# BareBonesArduino.net
KiCad netlist of a schematic drawn in EAGLE
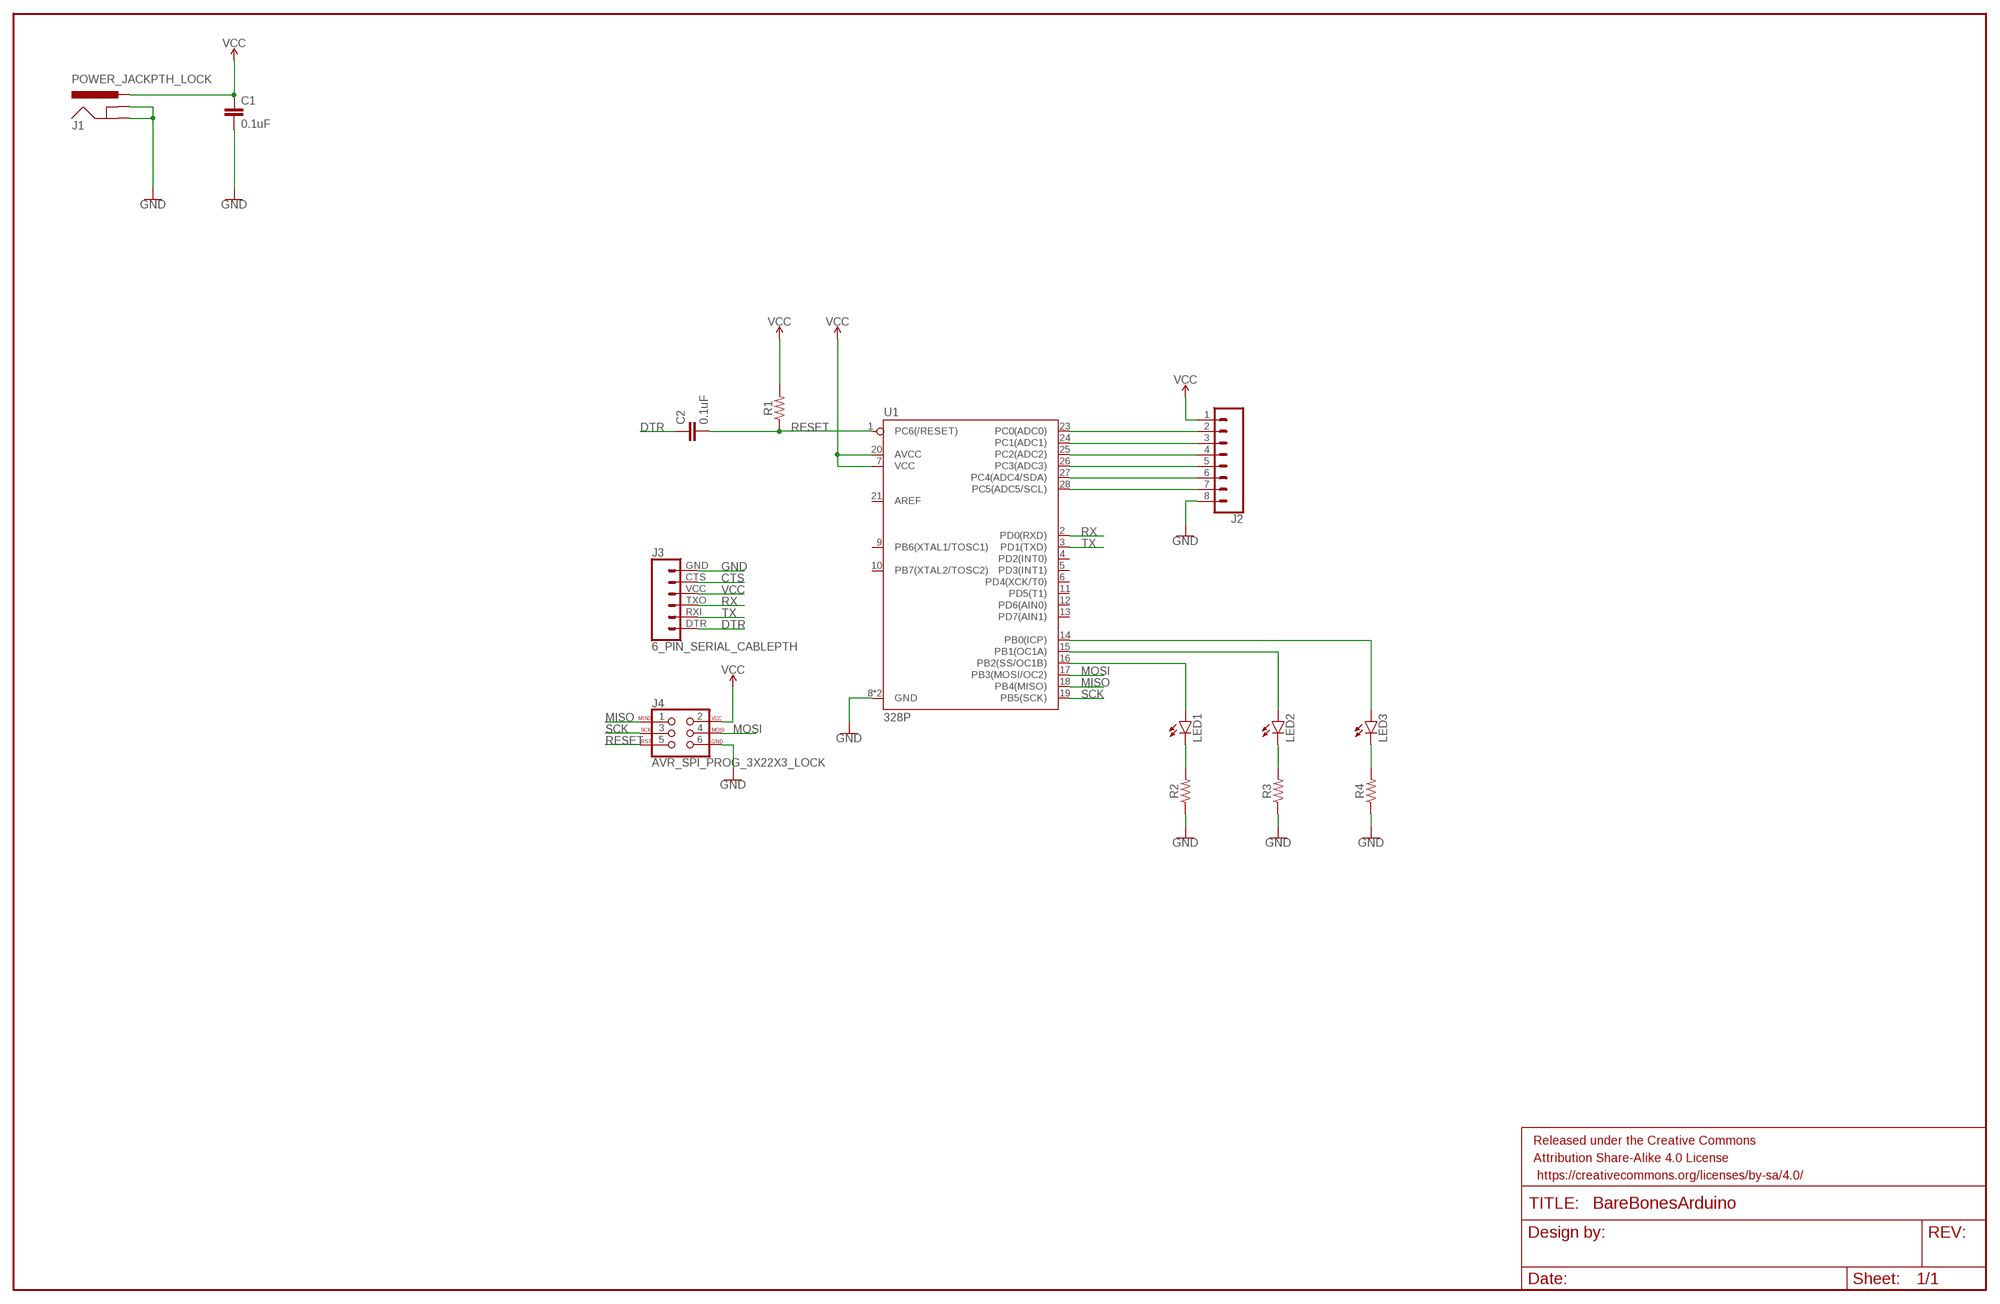
[diagram p0: schematic, sheet 1]

(export (version "E")
  (design (tool "Eeschema 10.0.6"))
  (components
    (comp (ref "C1")
      (value "0.1uF")
      (footprint "eagle-import:CAP-PTH-SMALL-KIT")
      (libsource (lib "eagle-import") (part "0.1UF-KIT-EZ-50V-20%"))
    )
    (comp (ref "C2")
      (value "0.1uF")
      (footprint "eagle-import:CAP-PTH-SMALL-KIT")
      (libsource (lib "eagle-import") (part "0.1UF-KIT-EZ-50V-20%"))
    )
    (comp (ref "FRAME1")
      (value "FRAME-LEDGER")
      (footprint "eagle-import:CREATIVE_COMMONS")
      (libsource (lib "eagle-import") (part "FRAME-LEDGER"))
    )
    (comp (ref "J1")
      (value "POWER_JACKPTH_LOCK")
      (footprint "eagle-import:POWER_JACK_PTH_LOCK")
      (libsource (lib "eagle-import") (part "POWER_JACKPTH_LOCK"))
    )
    (comp (ref "J2")
      (value "CONN_08\"")
      (footprint "eagle-import:1X08")
      (libsource (lib "eagle-import") (part "CONN_08{dblquote}"))
    )
    (comp (ref "J3")
      (value "6_PIN_SERIAL_CABLEPTH")
      (footprint "eagle-import:FTDI_BASIC")
      (libsource (lib "eagle-import") (part "6_PIN_SERIAL_CABLEPTH"))
    )
    (comp (ref "J4")
      (value "AVR_SPI_PROG_3X22X3_LOCK")
      (footprint "eagle-import:2X3_LOCK")
      (libsource (lib "eagle-import") (part "AVR_SPI_PROG_3X22X3_LOCK"))
    )
    (comp (ref "LED1")
      (value "LED5MM")
      (footprint "eagle-import:LED5MM")
      (libsource (lib "eagle-import") (part "LED5MM"))
    )
    (comp (ref "LED2")
      (value "LED5MM")
      (footprint "eagle-import:LED5MM")
      (libsource (lib "eagle-import") (part "LED5MM"))
    )
    (comp (ref "LED3")
      (value "LED5MM")
      (footprint "eagle-import:LED5MM")
      (libsource (lib "eagle-import") (part "LED5MM"))
    )
    (comp (ref "R1")
      (value "RESISTORAXIAL-0.3")
      (footprint "eagle-import:AXIAL-0.3")
      (libsource (lib "eagle-import") (part "RESISTORAXIAL-0.3"))
    )
    (comp (ref "R2")
      (value "RESISTORAXIAL-0.3")
      (footprint "eagle-import:AXIAL-0.3")
      (libsource (lib "eagle-import") (part "RESISTORAXIAL-0.3"))
    )
    (comp (ref "R3")
      (value "RESISTORAXIAL-0.3")
      (footprint "eagle-import:AXIAL-0.3")
      (libsource (lib "eagle-import") (part "RESISTORAXIAL-0.3"))
    )
    (comp (ref "R4")
      (value "RESISTORAXIAL-0.3")
      (footprint "eagle-import:AXIAL-0.3")
      (libsource (lib "eagle-import") (part "RESISTORAXIAL-0.3"))
    )
    (comp (ref "U1")
      (value "328P")
      (footprint "eagle-import:DIP28")
      (libsource (lib "eagle-import") (part "ATMEGA328P_PDIP"))
    )
  )
  (nets
    (net (code "1") (name "/CTS") (class "Default")
      (node (ref "J3") (pin "CTS") (pinfunction "5_CTS") (pintype "passive"))
    )
    (net (code "2") (name "/DTR") (class "Default")
      (node (ref "C2") (pin "1") (pinfunction "1_1") (pintype "passive"))
      (node (ref "J3") (pin "DTR") (pinfunction "1_DTR") (pintype "passive"))
    )
    (net (code "3") (name "/MISO") (class "Default")
      (node (ref "J4") (pin "1") (pinfunction "1_1") (pintype "passive"))
      (node (ref "U1") (pin "18") (pinfunction "PB4(MISO)_18") (pintype "bidirectional"))
    )
    (net (code "4") (name "/MOSI") (class "Default")
      (node (ref "J4") (pin "4") (pinfunction "4_4") (pintype "passive"))
      (node (ref "U1") (pin "17") (pinfunction "PB3(MOSI/OC2)_17") (pintype "bidirectional"))
    )
    (net (code "5") (name "/RESET") (class "Default")
      (node (ref "C2") (pin "2") (pinfunction "2_2") (pintype "passive"))
      (node (ref "J4") (pin "5") (pinfunction "5_5") (pintype "passive"))
      (node (ref "R1") (pin "P$1") (pinfunction "1_P$1") (pintype "passive"))
      (node (ref "U1") (pin "1") (pinfunction "PC6(/RESET)_1") (pintype "bidirectional"))
    )
    (net (code "6") (name "/RX") (class "Default")
      (node (ref "J3") (pin "TXO") (pinfunction "3_TXO") (pintype "passive"))
      (node (ref "U1") (pin "2") (pinfunction "PD0(RXD)_2") (pintype "bidirectional"))
    )
    (net (code "7") (name "/SCK") (class "Default")
      (node (ref "J4") (pin "3") (pinfunction "3_3") (pintype "passive"))
      (node (ref "U1") (pin "19") (pinfunction "PB5(SCK)_19") (pintype "bidirectional"))
    )
    (net (code "8") (name "/TX") (class "Default")
      (node (ref "J3") (pin "RXI") (pinfunction "2_RXI") (pintype "passive"))
      (node (ref "U1") (pin "3") (pinfunction "PD1(TXD)_3") (pintype "bidirectional"))
    )
    (net (code "9") (name "GND") (class "Default")
      (node (ref "C1") (pin "2") (pinfunction "2_2") (pintype "passive"))
      (node (ref "J1") (pin "GND") (pinfunction "GND_GND") (pintype "bidirectional"))
      (node (ref "J1") (pin "GNDBREAK") (pinfunction "GNDBREAK_GNDBREAK") (pintype "bidirectional"))
      (node (ref "J2") (pin "8") (pinfunction "8_8") (pintype "passive"))
      (node (ref "J3") (pin "GND") (pinfunction "6_GND") (pintype "passive"))
      (node (ref "J4") (pin "6") (pinfunction "6_6") (pintype "passive"))
      (node (ref "R2") (pin "P$1") (pinfunction "1_P$1") (pintype "passive"))
      (node (ref "R3") (pin "P$1") (pinfunction "1_P$1") (pintype "passive"))
      (node (ref "R4") (pin "P$1") (pinfunction "1_P$1") (pintype "passive"))
      (node (ref "U1") (pin "22") (pinfunction "GND_22") (pintype "bidirectional"))
      (node (ref "U1") (pin "8") (pinfunction "GND_8") (pintype "bidirectional"))
    )
    (net (code "10") (name "Net-(LED1-C)") (class "Default")
      (node (ref "LED1") (pin "K") (pinfunction "C_K") (pintype "passive"))
      (node (ref "R2") (pin "P$2") (pinfunction "2_P$2") (pintype "passive"))
    )
    (net (code "11") (name "Net-(LED2-C)") (class "Default")
      (node (ref "LED2") (pin "K") (pinfunction "C_K") (pintype "passive"))
      (node (ref "R3") (pin "P$2") (pinfunction "2_P$2") (pintype "passive"))
    )
    (net (code "12") (name "Net-(LED3-C)") (class "Default")
      (node (ref "LED3") (pin "K") (pinfunction "C_K") (pintype "passive"))
      (node (ref "R4") (pin "P$2") (pinfunction "2_P$2") (pintype "passive"))
    )
    (net (code "13") (name "Net-(U1-PB0(ICP))") (class "Default")
      (node (ref "LED3") (pin "A") (pinfunction "A_A") (pintype "passive"))
      (node (ref "U1") (pin "14") (pinfunction "PB0(ICP)_14") (pintype "bidirectional"))
    )
    (net (code "14") (name "Net-(U1-PB1(OC1A))") (class "Default")
      (node (ref "LED2") (pin "A") (pinfunction "A_A") (pintype "passive"))
      (node (ref "U1") (pin "15") (pinfunction "PB1(OC1A)_15") (pintype "bidirectional"))
    )
    (net (code "15") (name "Net-(U1-PB2(SS{slash}OC1B))") (class "Default")
      (node (ref "LED1") (pin "A") (pinfunction "A_A") (pintype "passive"))
      (node (ref "U1") (pin "16") (pinfunction "PB2(SS/OC1B)_16") (pintype "bidirectional"))
    )
    (net (code "16") (name "Net-(U1-PC0(ADC0))") (class "Default")
      (node (ref "J2") (pin "2") (pinfunction "2_2") (pintype "passive"))
      (node (ref "U1") (pin "23") (pinfunction "PC0(ADC0)_23") (pintype "bidirectional"))
    )
    (net (code "17") (name "Net-(U1-PC1(ADC1))") (class "Default")
      (node (ref "J2") (pin "3") (pinfunction "3_3") (pintype "passive"))
      (node (ref "U1") (pin "24") (pinfunction "PC1(ADC1)_24") (pintype "bidirectional"))
    )
    (net (code "18") (name "Net-(U1-PC2(ADC2))") (class "Default")
      (node (ref "J2") (pin "4") (pinfunction "4_4") (pintype "passive"))
      (node (ref "U1") (pin "25") (pinfunction "PC2(ADC2)_25") (pintype "bidirectional"))
    )
    (net (code "19") (name "Net-(U1-PC3(ADC3))") (class "Default")
      (node (ref "J2") (pin "5") (pinfunction "5_5") (pintype "passive"))
      (node (ref "U1") (pin "26") (pinfunction "PC3(ADC3)_26") (pintype "bidirectional"))
    )
    (net (code "20") (name "Net-(U1-PC4(ADC4{slash}SDA))") (class "Default")
      (node (ref "J2") (pin "6") (pinfunction "6_6") (pintype "passive"))
      (node (ref "U1") (pin "27") (pinfunction "PC4(ADC4/SDA)_27") (pintype "bidirectional"))
    )
    (net (code "21") (name "Net-(U1-PC5(ADC5{slash}SCL))") (class "Default")
      (node (ref "J2") (pin "7") (pinfunction "7_7") (pintype "passive"))
      (node (ref "U1") (pin "28") (pinfunction "PC5(ADC5/SCL)_28") (pintype "bidirectional"))
    )
    (net (code "22") (name "VCC") (class "Default")
      (node (ref "C1") (pin "1") (pinfunction "1_1") (pintype "passive"))
      (node (ref "J1") (pin "PWR") (pinfunction "PWR_PWR") (pintype "bidirectional"))
      (node (ref "J2") (pin "1") (pinfunction "1_1") (pintype "passive"))
      (node (ref "J3") (pin "VCC") (pinfunction "4_VCC") (pintype "passive"))
      (node (ref "J4") (pin "2") (pinfunction "2_2") (pintype "passive"))
      (node (ref "R1") (pin "P$2") (pinfunction "2_P$2") (pintype "passive"))
      (node (ref "U1") (pin "20") (pinfunction "AVCC_20") (pintype "bidirectional"))
      (node (ref "U1") (pin "7") (pinfunction "VCC_7") (pintype "bidirectional"))
    )
    (net (code "23") (name "unconnected-(U1-AREF-Pad21)") (class "Default")
      (node (ref "U1") (pin "21") (pinfunction "AREF_21") (pintype "bidirectional"))
    )
    (net (code "24") (name "unconnected-(U1-PB6(XTAL1{slash}TOSC1)-Pad9)") (class "Default")
      (node (ref "U1") (pin "9") (pinfunction "PB6(XTAL1/TOSC1)_9") (pintype "bidirectional"))
    )
    (net (code "25") (name "unconnected-(U1-PB7(XTAL2{slash}TOSC2)-Pad10)") (class "Default")
      (node (ref "U1") (pin "10") (pinfunction "PB7(XTAL2/TOSC2)_10") (pintype "bidirectional"))
    )
    (net (code "26") (name "unconnected-(U1-PD2(INT0)-Pad4)") (class "Default")
      (node (ref "U1") (pin "4") (pinfunction "PD2(INT0)_4") (pintype "bidirectional"))
    )
    (net (code "27") (name "unconnected-(U1-PD3(INT1)-Pad5)") (class "Default")
      (node (ref "U1") (pin "5") (pinfunction "PD3(INT1)_5") (pintype "bidirectional"))
    )
    (net (code "28") (name "unconnected-(U1-PD4(XCK{slash}T0)-Pad6)") (class "Default")
      (node (ref "U1") (pin "6") (pinfunction "PD4(XCK/T0)_6") (pintype "bidirectional"))
    )
    (net (code "29") (name "unconnected-(U1-PD5(T1)-Pad11)") (class "Default")
      (node (ref "U1") (pin "11") (pinfunction "PD5(T1)_11") (pintype "bidirectional"))
    )
    (net (code "30") (name "unconnected-(U1-PD6(AIN0)-Pad12)") (class "Default")
      (node (ref "U1") (pin "12") (pinfunction "PD6(AIN0)_12") (pintype "bidirectional"))
    )
    (net (code "31") (name "unconnected-(U1-PD7(AIN1)-Pad13)") (class "Default")
      (node (ref "U1") (pin "13") (pinfunction "PD7(AIN1)_13") (pintype "bidirectional"))
    )
  )
)
